# DotMatrixDigitalClockDisplay.net
KiCad netlist of a schematic drawn in EAGLE
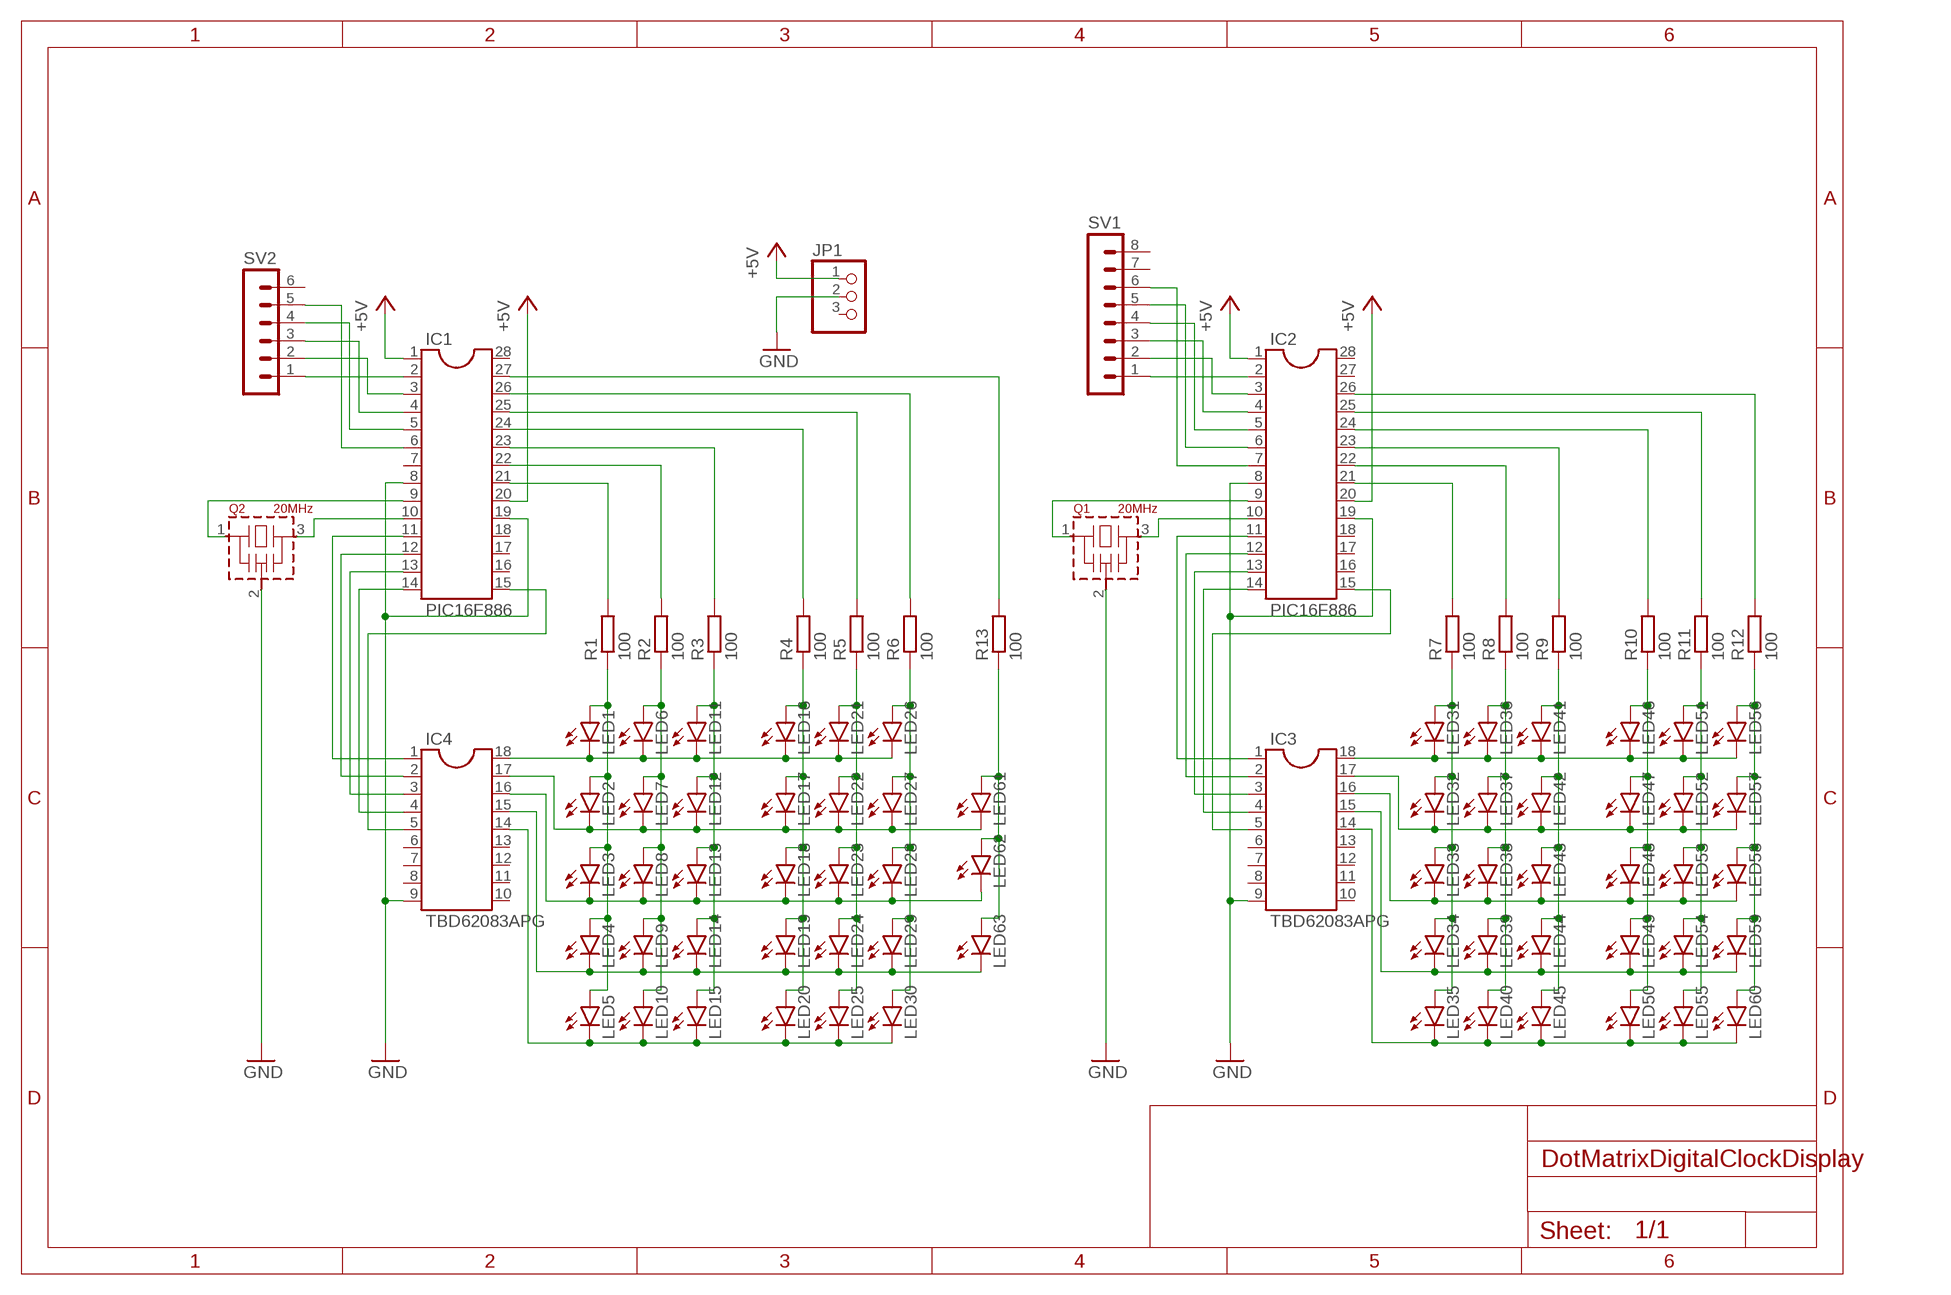
[diagram p0: schematic, sheet 1]

(export (version "E")
  (design (tool "Eeschema 10.0.6"))
  (components
    (comp (ref "IC1")
      (value "PIC16F886")
      (footprint "eagle-import:DIL28-3")
      (libsource (lib "eagle-import") (part "DIL28-3"))
    )
    (comp (ref "IC2")
      (value "PIC16F886")
      (footprint "eagle-import:DIL28-3")
      (libsource (lib "eagle-import") (part "DIL28-3"))
    )
    (comp (ref "IC3")
      (value "TBD62083APG")
      (footprint "eagle-import:DIL18")
      (libsource (lib "eagle-import") (part "DIL18"))
    )
    (comp (ref "IC4")
      (value "TBD62083APG")
      (footprint "eagle-import:DIL18")
      (libsource (lib "eagle-import") (part "DIL18"))
    )
    (comp (ref "JP1")
      (value "PINHD-1X3")
      (footprint "eagle-import:1X03")
      (libsource (lib "eagle-import") (part "PINHD-1X3"))
    )
    (comp (ref "LED1")
      (value "LED5MM")
      (footprint "eagle-import:LED5MM")
      (libsource (lib "eagle-import") (part "LED5MM"))
    )
    (comp (ref "LED2")
      (value "LED5MM")
      (footprint "eagle-import:LED5MM")
      (libsource (lib "eagle-import") (part "LED5MM"))
    )
    (comp (ref "LED3")
      (value "LED5MM")
      (footprint "eagle-import:LED5MM")
      (libsource (lib "eagle-import") (part "LED5MM"))
    )
    (comp (ref "LED4")
      (value "LED5MM")
      (footprint "eagle-import:LED5MM")
      (libsource (lib "eagle-import") (part "LED5MM"))
    )
    (comp (ref "LED5")
      (value "LED5MM")
      (footprint "eagle-import:LED5MM")
      (libsource (lib "eagle-import") (part "LED5MM"))
    )
    (comp (ref "LED6")
      (value "LED5MM")
      (footprint "eagle-import:LED5MM")
      (libsource (lib "eagle-import") (part "LED5MM"))
    )
    (comp (ref "LED7")
      (value "LED5MM")
      (footprint "eagle-import:LED5MM")
      (libsource (lib "eagle-import") (part "LED5MM"))
    )
    (comp (ref "LED8")
      (value "LED5MM")
      (footprint "eagle-import:LED5MM")
      (libsource (lib "eagle-import") (part "LED5MM"))
    )
    (comp (ref "LED9")
      (value "LED5MM")
      (footprint "eagle-import:LED5MM")
      (libsource (lib "eagle-import") (part "LED5MM"))
    )
    (comp (ref "LED10")
      (value "LED5MM")
      (footprint "eagle-import:LED5MM")
      (libsource (lib "eagle-import") (part "LED5MM"))
    )
    (comp (ref "LED11")
      (value "LED5MM")
      (footprint "eagle-import:LED5MM")
      (libsource (lib "eagle-import") (part "LED5MM"))
    )
    (comp (ref "LED12")
      (value "LED5MM")
      (footprint "eagle-import:LED5MM")
      (libsource (lib "eagle-import") (part "LED5MM"))
    )
    (comp (ref "LED13")
      (value "LED5MM")
      (footprint "eagle-import:LED5MM")
      (libsource (lib "eagle-import") (part "LED5MM"))
    )
    (comp (ref "LED14")
      (value "LED5MM")
      (footprint "eagle-import:LED5MM")
      (libsource (lib "eagle-import") (part "LED5MM"))
    )
    (comp (ref "LED15")
      (value "LED5MM")
      (footprint "eagle-import:LED5MM")
      (libsource (lib "eagle-import") (part "LED5MM"))
    )
    (comp (ref "LED16")
      (value "LED5MM")
      (footprint "eagle-import:LED5MM")
      (libsource (lib "eagle-import") (part "LED5MM"))
    )
    (comp (ref "LED17")
      (value "LED5MM")
      (footprint "eagle-import:LED5MM")
      (libsource (lib "eagle-import") (part "LED5MM"))
    )
    (comp (ref "LED18")
      (value "LED5MM")
      (footprint "eagle-import:LED5MM")
      (libsource (lib "eagle-import") (part "LED5MM"))
    )
    (comp (ref "LED19")
      (value "LED5MM")
      (footprint "eagle-import:LED5MM")
      (libsource (lib "eagle-import") (part "LED5MM"))
    )
    (comp (ref "LED20")
      (value "LED5MM")
      (footprint "eagle-import:LED5MM")
      (libsource (lib "eagle-import") (part "LED5MM"))
    )
    (comp (ref "LED21")
      (value "LED5MM")
      (footprint "eagle-import:LED5MM")
      (libsource (lib "eagle-import") (part "LED5MM"))
    )
    (comp (ref "LED22")
      (value "LED5MM")
      (footprint "eagle-import:LED5MM")
      (libsource (lib "eagle-import") (part "LED5MM"))
    )
    (comp (ref "LED23")
      (value "LED5MM")
      (footprint "eagle-import:LED5MM")
      (libsource (lib "eagle-import") (part "LED5MM"))
    )
    (comp (ref "LED24")
      (value "LED5MM")
      (footprint "eagle-import:LED5MM")
      (libsource (lib "eagle-import") (part "LED5MM"))
    )
    (comp (ref "LED25")
      (value "LED5MM")
      (footprint "eagle-import:LED5MM")
      (libsource (lib "eagle-import") (part "LED5MM"))
    )
    (comp (ref "LED26")
      (value "LED5MM")
      (footprint "eagle-import:LED5MM")
      (libsource (lib "eagle-import") (part "LED5MM"))
    )
    (comp (ref "LED27")
      (value "LED5MM")
      (footprint "eagle-import:LED5MM")
      (libsource (lib "eagle-import") (part "LED5MM"))
    )
    (comp (ref "LED28")
      (value "LED5MM")
      (footprint "eagle-import:LED5MM")
      (libsource (lib "eagle-import") (part "LED5MM"))
    )
    (comp (ref "LED29")
      (value "LED5MM")
      (footprint "eagle-import:LED5MM")
      (libsource (lib "eagle-import") (part "LED5MM"))
    )
    (comp (ref "LED30")
      (value "LED5MM")
      (footprint "eagle-import:LED5MM")
      (libsource (lib "eagle-import") (part "LED5MM"))
    )
    (comp (ref "LED31")
      (value "LED5MM")
      (footprint "eagle-import:LED5MM")
      (libsource (lib "eagle-import") (part "LED5MM"))
    )
    (comp (ref "LED32")
      (value "LED5MM")
      (footprint "eagle-import:LED5MM")
      (libsource (lib "eagle-import") (part "LED5MM"))
    )
    (comp (ref "LED33")
      (value "LED5MM")
      (footprint "eagle-import:LED5MM")
      (libsource (lib "eagle-import") (part "LED5MM"))
    )
    (comp (ref "LED34")
      (value "LED5MM")
      (footprint "eagle-import:LED5MM")
      (libsource (lib "eagle-import") (part "LED5MM"))
    )
    (comp (ref "LED35")
      (value "LED5MM")
      (footprint "eagle-import:LED5MM")
      (libsource (lib "eagle-import") (part "LED5MM"))
    )
    (comp (ref "LED36")
      (value "LED5MM")
      (footprint "eagle-import:LED5MM")
      (libsource (lib "eagle-import") (part "LED5MM"))
    )
    (comp (ref "LED37")
      (value "LED5MM")
      (footprint "eagle-import:LED5MM")
      (libsource (lib "eagle-import") (part "LED5MM"))
    )
    (comp (ref "LED38")
      (value "LED5MM")
      (footprint "eagle-import:LED5MM")
      (libsource (lib "eagle-import") (part "LED5MM"))
    )
    (comp (ref "LED39")
      (value "LED5MM")
      (footprint "eagle-import:LED5MM")
      (libsource (lib "eagle-import") (part "LED5MM"))
    )
    (comp (ref "LED40")
      (value "LED5MM")
      (footprint "eagle-import:LED5MM")
      (libsource (lib "eagle-import") (part "LED5MM"))
    )
    (comp (ref "LED41")
      (value "LED5MM")
      (footprint "eagle-import:LED5MM")
      (libsource (lib "eagle-import") (part "LED5MM"))
    )
    (comp (ref "LED42")
      (value "LED5MM")
      (footprint "eagle-import:LED5MM")
      (libsource (lib "eagle-import") (part "LED5MM"))
    )
    (comp (ref "LED43")
      (value "LED5MM")
      (footprint "eagle-import:LED5MM")
      (libsource (lib "eagle-import") (part "LED5MM"))
    )
    (comp (ref "LED44")
      (value "LED5MM")
      (footprint "eagle-import:LED5MM")
      (libsource (lib "eagle-import") (part "LED5MM"))
    )
    (comp (ref "LED45")
      (value "LED5MM")
      (footprint "eagle-import:LED5MM")
      (libsource (lib "eagle-import") (part "LED5MM"))
    )
    (comp (ref "LED46")
      (value "LED5MM")
      (footprint "eagle-import:LED5MM")
      (libsource (lib "eagle-import") (part "LED5MM"))
    )
    (comp (ref "LED47")
      (value "LED5MM")
      (footprint "eagle-import:LED5MM")
      (libsource (lib "eagle-import") (part "LED5MM"))
    )
    (comp (ref "LED48")
      (value "LED5MM")
      (footprint "eagle-import:LED5MM")
      (libsource (lib "eagle-import") (part "LED5MM"))
    )
    (comp (ref "LED49")
      (value "LED5MM")
      (footprint "eagle-import:LED5MM")
      (libsource (lib "eagle-import") (part "LED5MM"))
    )
    (comp (ref "LED50")
      (value "LED5MM")
      (footprint "eagle-import:LED5MM")
      (libsource (lib "eagle-import") (part "LED5MM"))
    )
    (comp (ref "LED51")
      (value "LED5MM")
      (footprint "eagle-import:LED5MM")
      (libsource (lib "eagle-import") (part "LED5MM"))
    )
    (comp (ref "LED52")
      (value "LED5MM")
      (footprint "eagle-import:LED5MM")
      (libsource (lib "eagle-import") (part "LED5MM"))
    )
    (comp (ref "LED53")
      (value "LED5MM")
      (footprint "eagle-import:LED5MM")
      (libsource (lib "eagle-import") (part "LED5MM"))
    )
    (comp (ref "LED54")
      (value "LED5MM")
      (footprint "eagle-import:LED5MM")
      (libsource (lib "eagle-import") (part "LED5MM"))
    )
    (comp (ref "LED55")
      (value "LED5MM")
      (footprint "eagle-import:LED5MM")
      (libsource (lib "eagle-import") (part "LED5MM"))
    )
    (comp (ref "LED56")
      (value "LED5MM")
      (footprint "eagle-import:LED5MM")
      (libsource (lib "eagle-import") (part "LED5MM"))
    )
    (comp (ref "LED57")
      (value "LED5MM")
      (footprint "eagle-import:LED5MM")
      (libsource (lib "eagle-import") (part "LED5MM"))
    )
    (comp (ref "LED58")
      (value "LED5MM")
      (footprint "eagle-import:LED5MM")
      (libsource (lib "eagle-import") (part "LED5MM"))
    )
    (comp (ref "LED59")
      (value "LED5MM")
      (footprint "eagle-import:LED5MM")
      (libsource (lib "eagle-import") (part "LED5MM"))
    )
    (comp (ref "LED60")
      (value "LED5MM")
      (footprint "eagle-import:LED5MM")
      (libsource (lib "eagle-import") (part "LED5MM"))
    )
    (comp (ref "LED61")
      (value "LED5MM")
      (footprint "eagle-import:LED5MM")
      (libsource (lib "eagle-import") (part "LED5MM"))
    )
    (comp (ref "LED62")
      (value "LED5MM")
      (footprint "eagle-import:LED5MM")
      (libsource (lib "eagle-import") (part "LED5MM"))
    )
    (comp (ref "LED63")
      (value "LED5MM")
      (footprint "eagle-import:LED5MM")
      (libsource (lib "eagle-import") (part "LED5MM"))
    )
    (comp (ref "Q1")
      (value "20MHz")
      (footprint "eagle-import:CSTLS_X")
      (libsource (lib "eagle-import") (part "CSTLS_X"))
    )
    (comp (ref "Q2")
      (value "20MHz")
      (footprint "eagle-import:CSTLS_X")
      (libsource (lib "eagle-import") (part "CSTLS_X"))
    )
    (comp (ref "R1")
      (value "100")
      (footprint "eagle-import:0207_7")
      (libsource (lib "eagle-import") (part "R-EU_0207/7"))
    )
    (comp (ref "R2")
      (value "100")
      (footprint "eagle-import:0207_7")
      (libsource (lib "eagle-import") (part "R-EU_0207/7"))
    )
    (comp (ref "R3")
      (value "100")
      (footprint "eagle-import:0207_7")
      (libsource (lib "eagle-import") (part "R-EU_0207/7"))
    )
    (comp (ref "R4")
      (value "100")
      (footprint "eagle-import:0207_7")
      (libsource (lib "eagle-import") (part "R-EU_0207/7"))
    )
    (comp (ref "R5")
      (value "100")
      (footprint "eagle-import:0207_7")
      (libsource (lib "eagle-import") (part "R-EU_0207/7"))
    )
    (comp (ref "R6")
      (value "100")
      (footprint "eagle-import:0207_7")
      (libsource (lib "eagle-import") (part "R-EU_0207/7"))
    )
    (comp (ref "R7")
      (value "100")
      (footprint "eagle-import:0207_7")
      (libsource (lib "eagle-import") (part "R-EU_0207/7"))
    )
    (comp (ref "R8")
      (value "100")
      (footprint "eagle-import:0207_7")
      (libsource (lib "eagle-import") (part "R-EU_0207/7"))
    )
    (comp (ref "R9")
      (value "100")
      (footprint "eagle-import:0207_7")
      (libsource (lib "eagle-import") (part "R-EU_0207/7"))
    )
    (comp (ref "R10")
      (value "100")
      (footprint "eagle-import:0207_7")
      (libsource (lib "eagle-import") (part "R-EU_0207/7"))
    )
    (comp (ref "R11")
      (value "100")
      (footprint "eagle-import:0207_7")
      (libsource (lib "eagle-import") (part "R-EU_0207/7"))
    )
    (comp (ref "R12")
      (value "100")
      (footprint "eagle-import:0207_7")
      (libsource (lib "eagle-import") (part "R-EU_0207/7"))
    )
    (comp (ref "R13")
      (value "100")
      (footprint "eagle-import:0207_7")
      (libsource (lib "eagle-import") (part "R-EU_0207/7"))
    )
    (comp (ref "SV1")
      (value "MA08-1")
      (footprint "eagle-import:MA08-1")
      (libsource (lib "eagle-import") (part "MA08-1"))
    )
    (comp (ref "SV2")
      (value "MA06-1")
      (footprint "eagle-import:MA06-1")
      (libsource (lib "eagle-import") (part "MA06-1"))
    )
  )
  (nets
    (net (code "1") (name "+5V") (class "Default")
      (node (ref "IC1") (pin "1") (pinfunction "1_1") (pintype "passive"))
      (node (ref "IC1") (pin "20") (pinfunction "20_20") (pintype "passive"))
      (node (ref "IC2") (pin "1") (pinfunction "1_1") (pintype "passive"))
      (node (ref "IC2") (pin "20") (pinfunction "20_20") (pintype "passive"))
      (node (ref "JP1") (pin "1") (pinfunction "1_1") (pintype "passive"))
    )
    (net (code "2") (name "GND") (class "Default")
      (node (ref "IC1") (pin "19") (pinfunction "19_19") (pintype "passive"))
      (node (ref "IC1") (pin "8") (pinfunction "8_8") (pintype "passive"))
      (node (ref "IC2") (pin "19") (pinfunction "19_19") (pintype "passive"))
      (node (ref "IC2") (pin "8") (pinfunction "8_8") (pintype "passive"))
      (node (ref "IC3") (pin "9") (pinfunction "9_9") (pintype "passive"))
      (node (ref "IC4") (pin "9") (pinfunction "9_9") (pintype "passive"))
      (node (ref "JP1") (pin "2") (pinfunction "2_2") (pintype "passive"))
      (node (ref "Q1") (pin "2") (pinfunction "VSS_2") (pintype "power_in"))
      (node (ref "Q2") (pin "2") (pinfunction "VSS_2") (pintype "power_in"))
    )
    (net (code "3") (name "Net-(IC1-Pad2)") (class "Default")
      (node (ref "IC1") (pin "2") (pinfunction "2_2") (pintype "passive"))
      (node (ref "SV2") (pin "1") (pinfunction "1_1") (pintype "passive"))
    )
    (net (code "4") (name "Net-(IC1-Pad3)") (class "Default")
      (node (ref "IC1") (pin "3") (pinfunction "3_3") (pintype "passive"))
      (node (ref "SV2") (pin "2") (pinfunction "2_2") (pintype "passive"))
    )
    (net (code "5") (name "Net-(IC1-Pad4)") (class "Default")
      (node (ref "IC1") (pin "4") (pinfunction "4_4") (pintype "passive"))
      (node (ref "SV2") (pin "3") (pinfunction "3_3") (pintype "passive"))
    )
    (net (code "6") (name "Net-(IC1-Pad5)") (class "Default")
      (node (ref "IC1") (pin "5") (pinfunction "5_5") (pintype "passive"))
      (node (ref "SV2") (pin "4") (pinfunction "4_4") (pintype "passive"))
    )
    (net (code "7") (name "Net-(IC1-Pad6)") (class "Default")
      (node (ref "IC1") (pin "6") (pinfunction "6_6") (pintype "passive"))
      (node (ref "SV2") (pin "5") (pinfunction "5_5") (pintype "passive"))
    )
    (net (code "8") (name "Net-(IC1-Pad9)") (class "Default")
      (node (ref "IC1") (pin "9") (pinfunction "9_9") (pintype "passive"))
      (node (ref "Q2") (pin "1") (pinfunction "1_1") (pintype "output"))
    )
    (net (code "9") (name "Net-(IC1-Pad10)") (class "Default")
      (node (ref "IC1") (pin "10") (pinfunction "10_10") (pintype "passive"))
      (node (ref "Q2") (pin "3") (pinfunction "3_3") (pintype "input"))
    )
    (net (code "10") (name "Net-(IC1-Pad11)") (class "Default")
      (node (ref "IC1") (pin "11") (pinfunction "11_11") (pintype "passive"))
      (node (ref "IC4") (pin "1") (pinfunction "1_1") (pintype "passive"))
    )
    (net (code "11") (name "Net-(IC1-Pad12)") (class "Default")
      (node (ref "IC1") (pin "12") (pinfunction "12_12") (pintype "passive"))
      (node (ref "IC4") (pin "2") (pinfunction "2_2") (pintype "passive"))
    )
    (net (code "12") (name "Net-(IC1-Pad13)") (class "Default")
      (node (ref "IC1") (pin "13") (pinfunction "13_13") (pintype "passive"))
      (node (ref "IC4") (pin "3") (pinfunction "3_3") (pintype "passive"))
    )
    (net (code "13") (name "Net-(IC1-Pad14)") (class "Default")
      (node (ref "IC1") (pin "14") (pinfunction "14_14") (pintype "passive"))
      (node (ref "IC4") (pin "4") (pinfunction "4_4") (pintype "passive"))
    )
    (net (code "14") (name "Net-(IC1-Pad15)") (class "Default")
      (node (ref "IC1") (pin "15") (pinfunction "15_15") (pintype "passive"))
      (node (ref "IC4") (pin "5") (pinfunction "5_5") (pintype "passive"))
    )
    (net (code "15") (name "Net-(IC1-Pad21)") (class "Default")
      (node (ref "IC1") (pin "21") (pinfunction "21_21") (pintype "passive"))
      (node (ref "R1") (pin "2") (pinfunction "2_2") (pintype "passive"))
    )
    (net (code "16") (name "Net-(IC1-Pad22)") (class "Default")
      (node (ref "IC1") (pin "22") (pinfunction "22_22") (pintype "passive"))
      (node (ref "R2") (pin "2") (pinfunction "2_2") (pintype "passive"))
    )
    (net (code "17") (name "Net-(IC1-Pad23)") (class "Default")
      (node (ref "IC1") (pin "23") (pinfunction "23_23") (pintype "passive"))
      (node (ref "R3") (pin "2") (pinfunction "2_2") (pintype "passive"))
    )
    (net (code "18") (name "Net-(IC1-Pad24)") (class "Default")
      (node (ref "IC1") (pin "24") (pinfunction "24_24") (pintype "passive"))
      (node (ref "R4") (pin "2") (pinfunction "2_2") (pintype "passive"))
    )
    (net (code "19") (name "Net-(IC1-Pad25)") (class "Default")
      (node (ref "IC1") (pin "25") (pinfunction "25_25") (pintype "passive"))
      (node (ref "R5") (pin "2") (pinfunction "2_2") (pintype "passive"))
    )
    (net (code "20") (name "Net-(IC1-Pad26)") (class "Default")
      (node (ref "IC1") (pin "26") (pinfunction "26_26") (pintype "passive"))
      (node (ref "R6") (pin "2") (pinfunction "2_2") (pintype "passive"))
    )
    (net (code "21") (name "Net-(IC1-Pad27)") (class "Default")
      (node (ref "IC1") (pin "27") (pinfunction "27_27") (pintype "passive"))
      (node (ref "R13") (pin "2") (pinfunction "2_2") (pintype "passive"))
    )
    (net (code "22") (name "Net-(IC2-Pad2)") (class "Default")
      (node (ref "IC2") (pin "2") (pinfunction "2_2") (pintype "passive"))
      (node (ref "SV1") (pin "1") (pinfunction "1_1") (pintype "passive"))
    )
    (net (code "23") (name "Net-(IC2-Pad3)") (class "Default")
      (node (ref "IC2") (pin "3") (pinfunction "3_3") (pintype "passive"))
      (node (ref "SV1") (pin "2") (pinfunction "2_2") (pintype "passive"))
    )
    (net (code "24") (name "Net-(IC2-Pad4)") (class "Default")
      (node (ref "IC2") (pin "4") (pinfunction "4_4") (pintype "passive"))
      (node (ref "SV1") (pin "3") (pinfunction "3_3") (pintype "passive"))
    )
    (net (code "25") (name "Net-(IC2-Pad5)") (class "Default")
      (node (ref "IC2") (pin "5") (pinfunction "5_5") (pintype "passive"))
      (node (ref "SV1") (pin "4") (pinfunction "4_4") (pintype "passive"))
    )
    (net (code "26") (name "Net-(IC2-Pad6)") (class "Default")
      (node (ref "IC2") (pin "6") (pinfunction "6_6") (pintype "passive"))
      (node (ref "SV1") (pin "5") (pinfunction "5_5") (pintype "passive"))
    )
    (net (code "27") (name "Net-(IC2-Pad7)") (class "Default")
      (node (ref "IC2") (pin "7") (pinfunction "7_7") (pintype "passive"))
      (node (ref "SV1") (pin "6") (pinfunction "6_6") (pintype "passive"))
    )
    (net (code "28") (name "Net-(IC2-Pad9)") (class "Default")
      (node (ref "IC2") (pin "9") (pinfunction "9_9") (pintype "passive"))
      (node (ref "Q1") (pin "1") (pinfunction "1_1") (pintype "output"))
    )
    (net (code "29") (name "Net-(IC2-Pad10)") (class "Default")
      (node (ref "IC2") (pin "10") (pinfunction "10_10") (pintype "passive"))
      (node (ref "Q1") (pin "3") (pinfunction "3_3") (pintype "input"))
    )
    (net (code "30") (name "Net-(IC2-Pad11)") (class "Default")
      (node (ref "IC2") (pin "11") (pinfunction "11_11") (pintype "passive"))
      (node (ref "IC3") (pin "1") (pinfunction "1_1") (pintype "passive"))
    )
    (net (code "31") (name "Net-(IC2-Pad12)") (class "Default")
      (node (ref "IC2") (pin "12") (pinfunction "12_12") (pintype "passive"))
      (node (ref "IC3") (pin "2") (pinfunction "2_2") (pintype "passive"))
    )
    (net (code "32") (name "Net-(IC2-Pad13)") (class "Default")
      (node (ref "IC2") (pin "13") (pinfunction "13_13") (pintype "passive"))
      (node (ref "IC3") (pin "3") (pinfunction "3_3") (pintype "passive"))
    )
    (net (code "33") (name "Net-(IC2-Pad14)") (class "Default")
      (node (ref "IC2") (pin "14") (pinfunction "14_14") (pintype "passive"))
      (node (ref "IC3") (pin "4") (pinfunction "4_4") (pintype "passive"))
    )
    (net (code "34") (name "Net-(IC2-Pad15)") (class "Default")
      (node (ref "IC2") (pin "15") (pinfunction "15_15") (pintype "passive"))
      (node (ref "IC3") (pin "5") (pinfunction "5_5") (pintype "passive"))
    )
    (net (code "35") (name "Net-(IC2-Pad21)") (class "Default")
      (node (ref "IC2") (pin "21") (pinfunction "21_21") (pintype "passive"))
      (node (ref "R7") (pin "2") (pinfunction "2_2") (pintype "passive"))
    )
    (net (code "36") (name "Net-(IC2-Pad22)") (class "Default")
      (node (ref "IC2") (pin "22") (pinfunction "22_22") (pintype "passive"))
      (node (ref "R8") (pin "2") (pinfunction "2_2") (pintype "passive"))
    )
    (net (code "37") (name "Net-(IC2-Pad23)") (class "Default")
      (node (ref "IC2") (pin "23") (pinfunction "23_23") (pintype "passive"))
      (node (ref "R9") (pin "2") (pinfunction "2_2") (pintype "passive"))
    )
    (net (code "38") (name "Net-(IC2-Pad24)") (class "Default")
      (node (ref "IC2") (pin "24") (pinfunction "24_24") (pintype "passive"))
      (node (ref "R10") (pin "2") (pinfunction "2_2") (pintype "passive"))
    )
    (net (code "39") (name "Net-(IC2-Pad25)") (class "Default")
      (node (ref "IC2") (pin "25") (pinfunction "25_25") (pintype "passive"))
      (node (ref "R11") (pin "2") (pinfunction "2_2") (pintype "passive"))
    )
    (net (code "40") (name "Net-(IC2-Pad26)") (class "Default")
      (node (ref "IC2") (pin "26") (pinfunction "26_26") (pintype "passive"))
      (node (ref "R12") (pin "2") (pinfunction "2_2") (pintype "passive"))
    )
    (net (code "41") (name "Net-(LED1-C)") (class "Default")
      (node (ref "IC4") (pin "18") (pinfunction "18_18") (pintype "passive"))
      (node (ref "LED1") (pin "K") (pinfunction "C_K") (pintype "passive"))
      (node (ref "LED11") (pin "K") (pinfunction "C_K") (pintype "passive"))
      (node (ref "LED16") (pin "K") (pinfunction "C_K") (pintype "passive"))
      (node (ref "LED21") (pin "K") (pinfunction "C_K") (pintype "passive"))
      (node (ref "LED26") (pin "K") (pinfunction "C_K") (pintype "passive"))
      (node (ref "LED6") (pin "K") (pinfunction "C_K") (pintype "passive"))
    )
    (net (code "42") (name "Net-(LED1-PadA)") (class "Default")
      (node (ref "LED1") (pin "A") (pinfunction "A_A") (pintype "passive"))
      (node (ref "LED2") (pin "A") (pinfunction "A_A") (pintype "passive"))
      (node (ref "LED3") (pin "A") (pinfunction "A_A") (pintype "passive"))
      (node (ref "LED4") (pin "A") (pinfunction "A_A") (pintype "passive"))
      (node (ref "LED5") (pin "A") (pinfunction "A_A") (pintype "passive"))
      (node (ref "R1") (pin "1") (pinfunction "1_1") (pintype "passive"))
    )
    (net (code "43") (name "Net-(LED10-C)") (class "Default")
      (node (ref "IC4") (pin "14") (pinfunction "14_14") (pintype "passive"))
      (node (ref "LED10") (pin "K") (pinfunction "C_K") (pintype "passive"))
      (node (ref "LED15") (pin "K") (pinfunction "C_K") (pintype "passive"))
      (node (ref "LED20") (pin "K") (pinfunction "C_K") (pintype "passive"))
      (node (ref "LED25") (pin "K") (pinfunction "C_K") (pintype "passive"))
      (node (ref "LED30") (pin "K") (pinfunction "C_K") (pintype "passive"))
      (node (ref "LED5") (pin "K") (pinfunction "C_K") (pintype "passive"))
    )
    (net (code "44") (name "Net-(LED10-PadA)") (class "Default")
      (node (ref "LED10") (pin "A") (pinfunction "A_A") (pintype "passive"))
      (node (ref "LED6") (pin "A") (pinfunction "A_A") (pintype "passive"))
      (node (ref "LED7") (pin "A") (pinfunction "A_A") (pintype "passive"))
      (node (ref "LED8") (pin "A") (pinfunction "A_A") (pintype "passive"))
      (node (ref "LED9") (pin "A") (pinfunction "A_A") (pintype "passive"))
      (node (ref "R2") (pin "1") (pinfunction "1_1") (pintype "passive"))
    )
    (net (code "45") (name "Net-(LED11-PadA)") (class "Default")
      (node (ref "LED11") (pin "A") (pinfunction "A_A") (pintype "passive"))
      (node (ref "LED12") (pin "A") (pinfunction "A_A") (pintype "passive"))
      (node (ref "LED13") (pin "A") (pinfunction "A_A") (pintype "passive"))
      (node (ref "LED14") (pin "A") (pinfunction "A_A") (pintype "passive"))
      (node (ref "LED15") (pin "A") (pinfunction "A_A") (pintype "passive"))
      (node (ref "R3") (pin "1") (pinfunction "1_1") (pintype "passive"))
    )
    (net (code "46") (name "Net-(LED12-C)") (class "Default")
      (node (ref "IC4") (pin "17") (pinfunction "17_17") (pintype "passive"))
      (node (ref "LED12") (pin "K") (pinfunction "C_K") (pintype "passive"))
      (node (ref "LED17") (pin "K") (pinfunction "C_K") (pintype "passive"))
      (node (ref "LED2") (pin "K") (pinfunction "C_K") (pintype "passive"))
      (node (ref "LED22") (pin "K") (pinfunction "C_K") (pintype "passive"))
      (node (ref "LED27") (pin "K") (pinfunction "C_K") (pintype "passive"))
      (node (ref "LED61") (pin "K") (pinfunction "C_K") (pintype "passive"))
      (node (ref "LED7") (pin "K") (pinfunction "C_K") (pintype "passive"))
    )
    (net (code "47") (name "Net-(LED13-C)") (class "Default")
      (node (ref "IC4") (pin "16") (pinfunction "16_16") (pintype "passive"))
      (node (ref "LED13") (pin "K") (pinfunction "C_K") (pintype "passive"))
      (node (ref "LED18") (pin "K") (pinfunction "C_K") (pintype "passive"))
      (node (ref "LED23") (pin "K") (pinfunction "C_K") (pintype "passive"))
      (node (ref "LED28") (pin "K") (pinfunction "C_K") (pintype "passive"))
      (node (ref "LED3") (pin "K") (pinfunction "C_K") (pintype "passive"))
      (node (ref "LED62") (pin "K") (pinfunction "C_K") (pintype "passive"))
      (node (ref "LED8") (pin "K") (pinfunction "C_K") (pintype "passive"))
    )
    (net (code "48") (name "Net-(LED14-C)") (class "Default")
      (node (ref "IC4") (pin "15") (pinfunction "15_15") (pintype "passive"))
      (node (ref "LED14") (pin "K") (pinfunction "C_K") (pintype "passive"))
      (node (ref "LED19") (pin "K") (pinfunction "C_K") (pintype "passive"))
      (node (ref "LED24") (pin "K") (pinfunction "C_K") (pintype "passive"))
      (node (ref "LED29") (pin "K") (pinfunction "C_K") (pintype "passive"))
      (node (ref "LED4") (pin "K") (pinfunction "C_K") (pintype "passive"))
      (node (ref "LED63") (pin "K") (pinfunction "C_K") (pintype "passive"))
      (node (ref "LED9") (pin "K") (pinfunction "C_K") (pintype "passive"))
    )
    (net (code "49") (name "Net-(LED16-PadA)") (class "Default")
      (node (ref "LED16") (pin "A") (pinfunction "A_A") (pintype "passive"))
      (node (ref "LED17") (pin "A") (pinfunction "A_A") (pintype "passive"))
      (node (ref "LED18") (pin "A") (pinfunction "A_A") (pintype "passive"))
      (node (ref "LED19") (pin "A") (pinfunction "A_A") (pintype "passive"))
      (node (ref "LED20") (pin "A") (pinfunction "A_A") (pintype "passive"))
      (node (ref "R4") (pin "1") (pinfunction "1_1") (pintype "passive"))
    )
    (net (code "50") (name "Net-(LED21-PadA)") (class "Default")
      (node (ref "LED21") (pin "A") (pinfunction "A_A") (pintype "passive"))
      (node (ref "LED22") (pin "A") (pinfunction "A_A") (pintype "passive"))
      (node (ref "LED23") (pin "A") (pinfunction "A_A") (pintype "passive"))
      (node (ref "LED24") (pin "A") (pinfunction "A_A") (pintype "passive"))
      (node (ref "LED25") (pin "A") (pinfunction "A_A") (pintype "passive"))
      (node (ref "R5") (pin "1") (pinfunction "1_1") (pintype "passive"))
    )
    (net (code "51") (name "Net-(LED26-PadA)") (class "Default")
      (node (ref "LED26") (pin "A") (pinfunction "A_A") (pintype "passive"))
      (node (ref "LED27") (pin "A") (pinfunction "A_A") (pintype "passive"))
      (node (ref "LED28") (pin "A") (pinfunction "A_A") (pintype "passive"))
      (node (ref "LED29") (pin "A") (pinfunction "A_A") (pintype "passive"))
      (node (ref "LED30") (pin "A") (pinfunction "A_A") (pintype "passive"))
      (node (ref "R6") (pin "1") (pinfunction "1_1") (pintype "passive"))
    )
    (net (code "52") (name "Net-(LED31-C)") (class "Default")
      (node (ref "IC3") (pin "18") (pinfunction "18_18") (pintype "passive"))
      (node (ref "LED31") (pin "K") (pinfunction "C_K") (pintype "passive"))
      (node (ref "LED36") (pin "K") (pinfunction "C_K") (pintype "passive"))
      (node (ref "LED41") (pin "K") (pinfunction "C_K") (pintype "passive"))
      (node (ref "LED46") (pin "K") (pinfunction "C_K") (pintype "passive"))
      (node (ref "LED51") (pin "K") (pinfunction "C_K") (pintype "passive"))
      (node (ref "LED56") (pin "K") (pinfunction "C_K") (pintype "passive"))
    )
    (net (code "53") (name "Net-(LED31-PadA)") (class "Default")
      (node (ref "LED31") (pin "A") (pinfunction "A_A") (pintype "passive"))
      (node (ref "LED32") (pin "A") (pinfunction "A_A") (pintype "passive"))
      (node (ref "LED33") (pin "A") (pinfunction "A_A") (pintype "passive"))
      (node (ref "LED34") (pin "A") (pinfunction "A_A") (pintype "passive"))
      (node (ref "LED35") (pin "A") (pinfunction "A_A") (pintype "passive"))
      (node (ref "R7") (pin "1") (pinfunction "1_1") (pintype "passive"))
    )
    (net (code "54") (name "Net-(LED32-C)") (class "Default")
      (node (ref "IC3") (pin "17") (pinfunction "17_17") (pintype "passive"))
      (node (ref "LED32") (pin "K") (pinfunction "C_K") (pintype "passive"))
      (node (ref "LED37") (pin "K") (pinfunction "C_K") (pintype "passive"))
      (node (ref "LED42") (pin "K") (pinfunction "C_K") (pintype "passive"))
      (node (ref "LED47") (pin "K") (pinfunction "C_K") (pintype "passive"))
      (node (ref "LED52") (pin "K") (pinfunction "C_K") (pintype "passive"))
      (node (ref "LED57") (pin "K") (pinfunction "C_K") (pintype "passive"))
    )
    (net (code "55") (name "Net-(LED33-C)") (class "Default")
      (node (ref "IC3") (pin "16") (pinfunction "16_16") (pintype "passive"))
      (node (ref "LED33") (pin "K") (pinfunction "C_K") (pintype "passive"))
      (node (ref "LED38") (pin "K") (pinfunction "C_K") (pintype "passive"))
      (node (ref "LED43") (pin "K") (pinfunction "C_K") (pintype "passive"))
      (node (ref "LED48") (pin "K") (pinfunction "C_K") (pintype "passive"))
      (node (ref "LED53") (pin "K") (pinfunction "C_K") (pintype "passive"))
      (node (ref "LED58") (pin "K") (pinfunction "C_K") (pintype "passive"))
    )
    (net (code "56") (name "Net-(LED34-C)") (class "Default")
      (node (ref "IC3") (pin "15") (pinfunction "15_15") (pintype "passive"))
      (node (ref "LED34") (pin "K") (pinfunction "C_K") (pintype "passive"))
      (node (ref "LED39") (pin "K") (pinfunction "C_K") (pintype "passive"))
      (node (ref "LED44") (pin "K") (pinfunction "C_K") (pintype "passive"))
      (node (ref "LED49") (pin "K") (pinfunction "C_K") (pintype "passive"))
      (node (ref "LED54") (pin "K") (pinfunction "C_K") (pintype "passive"))
      (node (ref "LED59") (pin "K") (pinfunction "C_K") (pintype "passive"))
    )
    (net (code "57") (name "Net-(LED35-C)") (class "Default")
      (node (ref "IC3") (pin "14") (pinfunction "14_14") (pintype "passive"))
      (node (ref "LED35") (pin "K") (pinfunction "C_K") (pintype "passive"))
      (node (ref "LED40") (pin "K") (pinfunction "C_K") (pintype "passive"))
      (node (ref "LED45") (pin "K") (pinfunction "C_K") (pintype "passive"))
      (node (ref "LED50") (pin "K") (pinfunction "C_K") (pintype "passive"))
      (node (ref "LED55") (pin "K") (pinfunction "C_K") (pintype "passive"))
      (node (ref "LED60") (pin "K") (pinfunction "C_K") (pintype "passive"))
    )
    (net (code "58") (name "Net-(LED36-PadA)") (class "Default")
      (node (ref "LED36") (pin "A") (pinfunction "A_A") (pintype "passive"))
      (node (ref "LED37") (pin "A") (pinfunction "A_A") (pintype "passive"))
      (node (ref "LED38") (pin "A") (pinfunction "A_A") (pintype "passive"))
      (node (ref "LED39") (pin "A") (pinfunction "A_A") (pintype "passive"))
      (node (ref "LED40") (pin "A") (pinfunction "A_A") (pintype "passive"))
      (node (ref "R8") (pin "1") (pinfunction "1_1") (pintype "passive"))
    )
    (net (code "59") (name "Net-(LED41-PadA)") (class "Default")
      (node (ref "LED41") (pin "A") (pinfunction "A_A") (pintype "passive"))
      (node (ref "LED42") (pin "A") (pinfunction "A_A") (pintype "passive"))
      (node (ref "LED43") (pin "A") (pinfunction "A_A") (pintype "passive"))
      (node (ref "LED44") (pin "A") (pinfunction "A_A") (pintype "passive"))
      (node (ref "LED45") (pin "A") (pinfunction "A_A") (pintype "passive"))
      (node (ref "R9") (pin "1") (pinfunction "1_1") (pintype "passive"))
    )
    (net (code "60") (name "Net-(LED46-PadA)") (class "Default")
      (node (ref "LED46") (pin "A") (pinfunction "A_A") (pintype "passive"))
      (node (ref "LED47") (pin "A") (pinfunction "A_A") (pintype "passive"))
      (node (ref "LED48") (pin "A") (pinfunction "A_A") (pintype "passive"))
      (node (ref "LED49") (pin "A") (pinfunction "A_A") (pintype "passive"))
      (node (ref "LED50") (pin "A") (pinfunction "A_A") (pintype "passive"))
      (node (ref "R10") (pin "1") (pinfunction "1_1") (pintype "passive"))
    )
    (net (code "61") (name "Net-(LED51-PadA)") (class "Default")
      (node (ref "LED51") (pin "A") (pinfunction "A_A") (pintype "passive"))
      (node (ref "LED52") (pin "A") (pinfunction "A_A") (pintype "passive"))
      (node (ref "LED53") (pin "A") (pinfunction "A_A") (pintype "passive"))
      (node (ref "LED54") (pin "A") (pinfunction "A_A") (pintype "passive"))
      (node (ref "LED55") (pin "A") (pinfunction "A_A") (pintype "passive"))
      (node (ref "R11") (pin "1") (pinfunction "1_1") (pintype "passive"))
    )
    (net (code "62") (name "Net-(LED56-PadA)") (class "Default")
      (node (ref "LED56") (pin "A") (pinfunction "A_A") (pintype "passive"))
      (node (ref "LED57") (pin "A") (pinfunction "A_A") (pintype "passive"))
      (node (ref "LED58") (pin "A") (pinfunction "A_A") (pintype "passive"))
      (node (ref "LED59") (pin "A") (pinfunction "A_A") (pintype "passive"))
      (node (ref "LED60") (pin "A") (pinfunction "A_A") (pintype "passive"))
      (node (ref "R12") (pin "1") (pinfunction "1_1") (pintype "passive"))
    )
    (net (code "63") (name "Net-(LED61-PadA)") (class "Default")
      (node (ref "LED61") (pin "A") (pinfunction "A_A") (pintype "passive"))
      (node (ref "LED62") (pin "A") (pinfunction "A_A") (pintype "passive"))
      (node (ref "LED63") (pin "A") (pinfunction "A_A") (pintype "passive"))
      (node (ref "R13") (pin "1") (pinfunction "1_1") (pintype "passive"))
    )
    (net (code "64") (name "unconnected-(IC1-Pad7)") (class "Default")
      (node (ref "IC1") (pin "7") (pinfunction "7_7") (pintype "passive"))
    )
    (net (code "65") (name "unconnected-(IC1-Pad16)") (class "Default")
      (node (ref "IC1") (pin "16") (pinfunction "16_16") (pintype "passive"))
    )
    (net (code "66") (name "unconnected-(IC1-Pad17)") (class "Default")
      (node (ref "IC1") (pin "17") (pinfunction "17_17") (pintype "passive"))
    )
    (net (code "67") (name "unconnected-(IC1-Pad18)") (class "Default")
      (node (ref "IC1") (pin "18") (pinfunction "18_18") (pintype "passive"))
    )
    (net (code "68") (name "unconnected-(IC1-Pad28)") (class "Default")
      (node (ref "IC1") (pin "28") (pinfunction "28_28") (pintype "passive"))
    )
    (net (code "69") (name "unconnected-(IC2-Pad16)") (class "Default")
      (node (ref "IC2") (pin "16") (pinfunction "16_16") (pintype "passive"))
    )
    (net (code "70") (name "unconnected-(IC2-Pad17)") (class "Default")
      (node (ref "IC2") (pin "17") (pinfunction "17_17") (pintype "passive"))
    )
    (net (code "71") (name "unconnected-(IC2-Pad18)") (class "Default")
      (node (ref "IC2") (pin "18") (pinfunction "18_18") (pintype "passive"))
    )
    (net (code "72") (name "unconnected-(IC2-Pad27)") (class "Default")
      (node (ref "IC2") (pin "27") (pinfunction "27_27") (pintype "passive"))
    )
    (net (code "73") (name "unconnected-(IC2-Pad28)") (class "Default")
      (node (ref "IC2") (pin "28") (pinfunction "28_28") (pintype "passive"))
    )
    (net (code "74") (name "unconnected-(IC3-Pad6)") (class "Default")
      (node (ref "IC3") (pin "6") (pinfunction "6_6") (pintype "passive"))
    )
    (net (code "75") (name "unconnected-(IC3-Pad7)") (class "Default")
      (node (ref "IC3") (pin "7") (pinfunction "7_7") (pintype "passive"))
    )
    (net (code "76") (name "unconnected-(IC3-Pad8)") (class "Default")
      (node (ref "IC3") (pin "8") (pinfunction "8_8") (pintype "passive"))
    )
    (net (code "77") (name "unconnected-(IC3-Pad10)") (class "Default")
      (node (ref "IC3") (pin "10") (pinfunction "10_10") (pintype "passive"))
    )
    (net (code "78") (name "unconnected-(IC3-Pad11)") (class "Default")
      (node (ref "IC3") (pin "11") (pinfunction "11_11") (pintype "passive"))
    )
    (net (code "79") (name "unconnected-(IC3-Pad12)") (class "Default")
      (node (ref "IC3") (pin "12") (pinfunction "12_12") (pintype "passive"))
    )
    (net (code "80") (name "unconnected-(IC3-Pad13)") (class "Default")
      (node (ref "IC3") (pin "13") (pinfunction "13_13") (pintype "passive"))
    )
    (net (code "81") (name "unconnected-(IC4-Pad6)") (class "Default")
      (node (ref "IC4") (pin "6") (pinfunction "6_6") (pintype "passive"))
    )
    (net (code "82") (name "unconnected-(IC4-Pad7)") (class "Default")
      (node (ref "IC4") (pin "7") (pinfunction "7_7") (pintype "passive"))
    )
    (net (code "83") (name "unconnected-(IC4-Pad8)") (class "Default")
      (node (ref "IC4") (pin "8") (pinfunction "8_8") (pintype "passive"))
    )
    (net (code "84") (name "unconnected-(IC4-Pad10)") (class "Default")
      (node (ref "IC4") (pin "10") (pinfunction "10_10") (pintype "passive"))
    )
    (net (code "85") (name "unconnected-(IC4-Pad11)") (class "Default")
      (node (ref "IC4") (pin "11") (pinfunction "11_11") (pintype "passive"))
    )
    (net (code "86") (name "unconnected-(IC4-Pad12)") (class "Default")
      (node (ref "IC4") (pin "12") (pinfunction "12_12") (pintype "passive"))
    )
    (net (code "87") (name "unconnected-(IC4-Pad13)") (class "Default")
      (node (ref "IC4") (pin "13") (pinfunction "13_13") (pintype "passive"))
    )
    (net (code "88") (name "unconnected-(JP1-Pad3)") (class "Default")
      (node (ref "JP1") (pin "3") (pinfunction "3_3") (pintype "passive"))
    )
    (net (code "89") (name "unconnected-(SV1-Pad7)") (class "Default")
      (node (ref "SV1") (pin "7") (pinfunction "7_7") (pintype "passive"))
    )
    (net (code "90") (name "unconnected-(SV1-Pad8)") (class "Default")
      (node (ref "SV1") (pin "8") (pinfunction "8_8") (pintype "passive"))
    )
    (net (code "91") (name "unconnected-(SV2-Pad6)") (class "Default")
      (node (ref "SV2") (pin "6") (pinfunction "6_6") (pintype "passive"))
    )
  )
)
